# mainboard.net
KiCad netlist of a schematic drawn in EAGLE
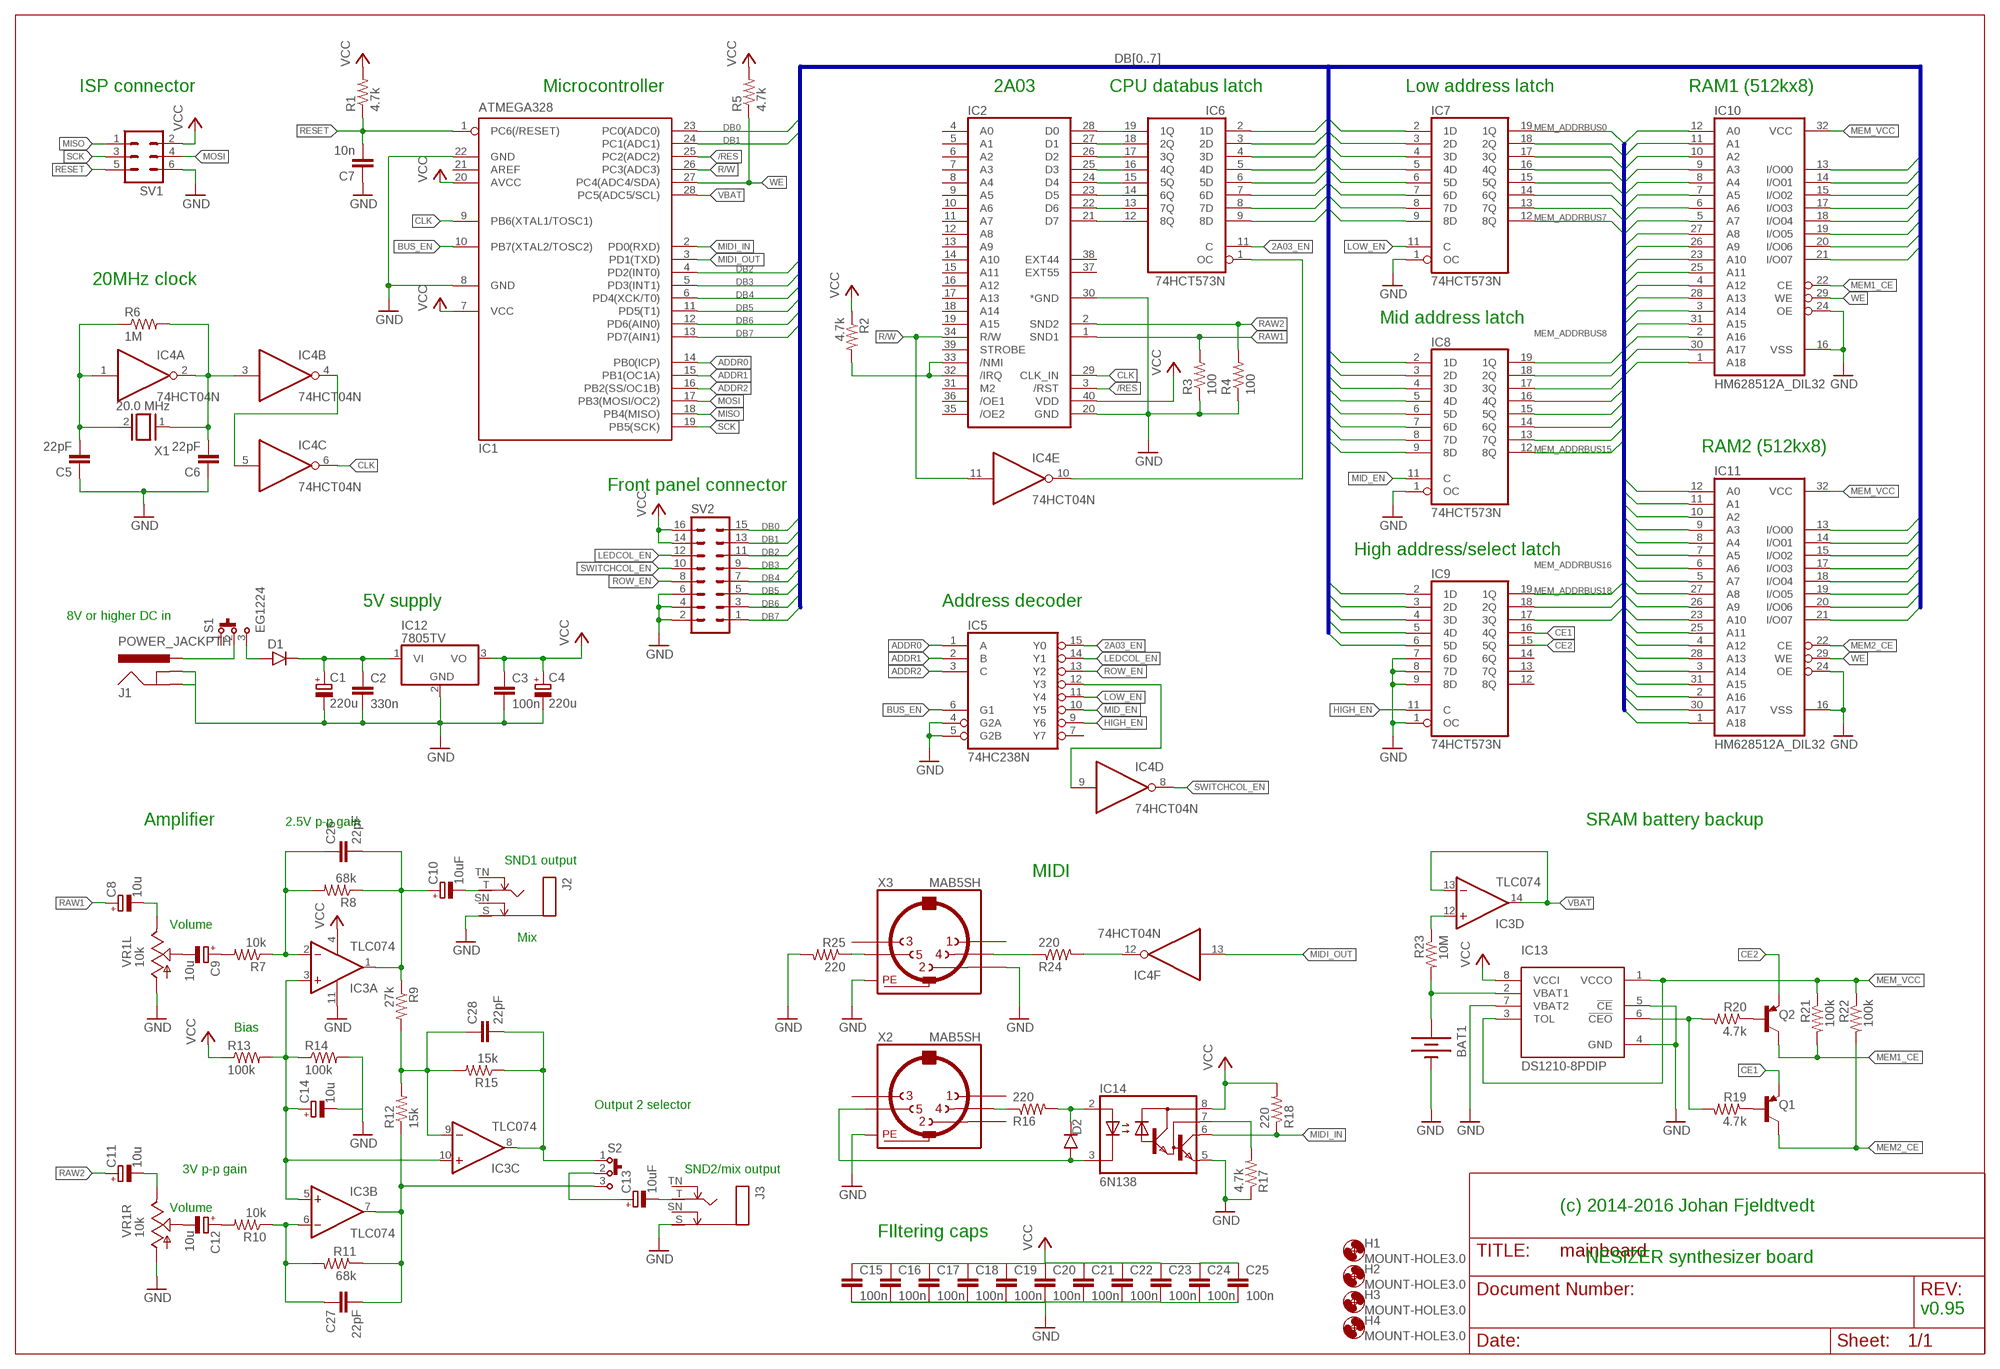
[diagram p0: schematic, sheet 1]

(export (version "E")
  (design (tool "Eeschema 10.0.6"))
  (components
    (comp (ref "BAT1")
      (value "BATTERY20PTH")
      (footprint "eagle-import:BATTCOM_20MM_PTH")
      (libsource (lib "eagle-import") (part "BATTERY20PTH"))
    )
    (comp (ref "C1")
      (value "220u")
      (footprint "eagle-import:E5-10,5")
      (libsource (lib "eagle-import") (part "CPOL-EUE5-10.5"))
    )
    (comp (ref "C2")
      (value "330n")
      (footprint "eagle-import:C025-025X050")
      (libsource (lib "eagle-import") (part "resistor_C-EU025-025X050"))
    )
    (comp (ref "C3")
      (value "100n")
      (footprint "eagle-import:C025-025X050")
      (libsource (lib "eagle-import") (part "C-EU025-025X050"))
    )
    (comp (ref "C4")
      (value "220u")
      (footprint "eagle-import:E5-10,5")
      (libsource (lib "eagle-import") (part "CPOL-EUE5-10.5"))
    )
    (comp (ref "C5")
      (value "22pF")
      (footprint "eagle-import:C2.5-2")
      (libsource (lib "eagle-import") (part "C2.5/2"))
    )
    (comp (ref "C6")
      (value "22pF")
      (footprint "eagle-import:C2.5-2")
      (libsource (lib "eagle-import") (part "C2.5/2"))
    )
    (comp (ref "C7")
      (value "10n")
      (footprint "eagle-import:C2.5-2")
      (libsource (lib "eagle-import") (part "C2.5/2"))
    )
    (comp (ref "C8")
      (value "10u")
      (footprint "eagle-import:E2-5")
      (libsource (lib "eagle-import") (part "CPOL-EUE2-5"))
    )
    (comp (ref "C9")
      (value "10u")
      (footprint "eagle-import:E2-5")
      (libsource (lib "eagle-import") (part "CPOL-EUE2-5"))
    )
    (comp (ref "C10")
      (value "10uF")
      (footprint "eagle-import:E2-5")
      (libsource (lib "eagle-import") (part "CPOL-EUE2-5"))
    )
    (comp (ref "C11")
      (value "10u")
      (footprint "eagle-import:E2-5")
      (libsource (lib "eagle-import") (part "CPOL-EUE2-5"))
    )
    (comp (ref "C12")
      (value "10u")
      (footprint "eagle-import:E2-5")
      (libsource (lib "eagle-import") (part "CPOL-EUE2-5"))
    )
    (comp (ref "C13")
      (value "10uF")
      (footprint "eagle-import:E2-5")
      (libsource (lib "eagle-import") (part "CPOL-EUE2-5"))
    )
    (comp (ref "C14")
      (value "10u")
      (footprint "eagle-import:E2-5")
      (libsource (lib "eagle-import") (part "CPOL-EUE2-5"))
    )
    (comp (ref "C15")
      (value "100n")
      (footprint "eagle-import:C025-025X050")
      (libsource (lib "eagle-import") (part "C-EU025-025X050"))
    )
    (comp (ref "C16")
      (value "100n")
      (footprint "eagle-import:C025-025X050")
      (libsource (lib "eagle-import") (part "C-EU025-025X050"))
    )
    (comp (ref "C17")
      (value "100n")
      (footprint "eagle-import:C025-025X050")
      (libsource (lib "eagle-import") (part "C-EU025-025X050"))
    )
    (comp (ref "C18")
      (value "100n")
      (footprint "eagle-import:C025-025X050")
      (libsource (lib "eagle-import") (part "C-EU025-025X050"))
    )
    (comp (ref "C19")
      (value "100n")
      (footprint "eagle-import:C025-025X050")
      (libsource (lib "eagle-import") (part "C-EU025-025X050"))
    )
    (comp (ref "C20")
      (value "100n")
      (footprint "eagle-import:C025-025X050")
      (libsource (lib "eagle-import") (part "C-EU025-025X050"))
    )
    (comp (ref "C21")
      (value "100n")
      (footprint "eagle-import:C025-025X050")
      (libsource (lib "eagle-import") (part "C-EU025-025X050"))
    )
    (comp (ref "C22")
      (value "100n")
      (footprint "eagle-import:C025-025X050")
      (libsource (lib "eagle-import") (part "C-EU025-025X050"))
    )
    (comp (ref "C23")
      (value "100n")
      (footprint "eagle-import:C025-025X050")
      (libsource (lib "eagle-import") (part "C-EU025-025X050"))
    )
    (comp (ref "C24")
      (value "100n")
      (footprint "eagle-import:C025-025X050")
      (libsource (lib "eagle-import") (part "C-EU025-025X050"))
    )
    (comp (ref "C25")
      (value "100n")
      (footprint "eagle-import:C025-025X050")
      (libsource (lib "eagle-import") (part "C-EU025-025X050"))
    )
    (comp (ref "C26")
      (value "22pF")
      (footprint "eagle-import:C2.5-2")
      (libsource (lib "eagle-import") (part "C2.5/2"))
    )
    (comp (ref "C27")
      (value "22pF")
      (footprint "eagle-import:C2.5-2")
      (libsource (lib "eagle-import") (part "C2.5/2"))
    )
    (comp (ref "C28")
      (value "22pF")
      (footprint "eagle-import:C2.5-2")
      (libsource (lib "eagle-import") (part "C2.5/2"))
    )
    (comp (ref "D1")
      (value "1N400X.3")
      (footprint "eagle-import:DO41-3")
      (libsource (lib "eagle-import") (part "1N400X.3"))
    )
    (comp (ref "D2")
      (value "1N914.3")
      (footprint "eagle-import:DO35-3")
      (libsource (lib "eagle-import") (part "1N914.3"))
    )
    (comp (ref "H1")
      (value "MOUNT-HOLE3.0")
      (footprint "eagle-import:3,0")
      (libsource (lib "eagle-import") (part "MOUNT-HOLE3.0"))
    )
    (comp (ref "H2")
      (value "MOUNT-HOLE3.0")
      (footprint "eagle-import:3,0")
      (libsource (lib "eagle-import") (part "MOUNT-HOLE3.0"))
    )
    (comp (ref "H3")
      (value "MOUNT-HOLE3.0")
      (footprint "eagle-import:3,0")
      (libsource (lib "eagle-import") (part "MOUNT-HOLE3.0"))
    )
    (comp (ref "H4")
      (value "MOUNT-HOLE3.0")
      (footprint "eagle-import:3,0")
      (libsource (lib "eagle-import") (part "MOUNT-HOLE3.0"))
    )
    (comp (ref "IC1")
      (value "ATMEGA328")
      (footprint "eagle-import:DIL28-3")
      (libsource (lib "eagle-import") (part "MEGA8-P"))
    )
    (comp (ref "IC2")
      (value "2A03")
      (footprint "eagle-import:DIL40")
      (libsource (lib "eagle-import") (part "2A03"))
    )
    (comp (ref "IC3")
      (value "TLC074")
      (footprint "eagle-import:DIL14")
      (libsource (lib "eagle-import") (part "TL074P"))
    )
    (comp (ref "IC4")
      (value "74HCT04N")
      (footprint "eagle-import:DIL14")
      (libsource (lib "eagle-import") (part "7404NHCT"))
    )
    (comp (ref "IC5")
      (value "74HC238N")
      (footprint "eagle-import:DIL16")
      (libsource (lib "eagle-import") (part "74138NHC"))
    )
    (comp (ref "IC6")
      (value "74HCT573N")
      (footprint "eagle-import:DIL20")
      (libsource (lib "eagle-import") (part "74573NHCT"))
    )
    (comp (ref "IC7")
      (value "74HCT573N")
      (footprint "eagle-import:DIL20")
      (libsource (lib "eagle-import") (part "74573NHCT"))
    )
    (comp (ref "IC8")
      (value "74HCT573N")
      (footprint "eagle-import:DIL20")
      (libsource (lib "eagle-import") (part "74573NHCT"))
    )
    (comp (ref "IC9")
      (value "74HCT573N")
      (footprint "eagle-import:DIL20")
      (libsource (lib "eagle-import") (part "74573NHCT"))
    )
    (comp (ref "IC10")
      (value "HM628512A_DIL32")
      (footprint "eagle-import:DIL32")
      (libsource (lib "eagle-import") (part "HM628512A_DIL32"))
    )
    (comp (ref "IC11")
      (value "HM628512A_DIL32")
      (footprint "eagle-import:DIL32")
      (libsource (lib "eagle-import") (part "HM628512A_DIL32"))
    )
    (comp (ref "IC12")
      (value "7805TV")
      (footprint "eagle-import:TO220V")
      (libsource (lib "eagle-import") (part "78TV05"))
    )
    (comp (ref "IC13")
      (value "DS1210-8PDIP")
      (footprint "eagle-import:DIL08")
      (libsource (lib "eagle-import") (part "DS1210-8PDIP"))
    )
    (comp (ref "IC14")
      (value "6N138")
      (footprint "eagle-import:DIL08")
      (fields (field (name "MF") "VISHAY/TELEFUNKEN"))
      (libsource (lib "eagle-import") (part "6N138"))
    )
    (comp (ref "J1")
      (value "POWER_JACKPTH")
      (footprint "eagle-import:POWER_JACK_PTH")
      (libsource (lib "eagle-import") (part "POWER_JACKPTH"))
    )
    (comp (ref "J2")
      (value "MONOSW")
      (footprint "eagle-import:NMJ4HCD2")
      (libsource (lib "eagle-import") (part "MONOSW"))
    )
    (comp (ref "J3")
      (value "MONOSW")
      (footprint "eagle-import:NMJ4HCD2")
      (libsource (lib "eagle-import") (part "MONOSW"))
    )
    (comp (ref "Q1")
      (value "BC557")
      (footprint "eagle-import:TO92")
      (libsource (lib "eagle-import") (part "BC557"))
    )
    (comp (ref "Q2")
      (value "BC557")
      (footprint "eagle-import:TO92")
      (libsource (lib "eagle-import") (part "BC557"))
    )
    (comp (ref "R1")
      (value "4.7k")
      (footprint "eagle-import:0207_7")
      (libsource (lib "eagle-import") (part "R-US_0207/7"))
    )
    (comp (ref "R2")
      (value "4.7k")
      (footprint "eagle-import:0207_7")
      (libsource (lib "eagle-import") (part "R-US_0207/7"))
    )
    (comp (ref "R3")
      (value "100")
      (footprint "eagle-import:0207_7")
      (libsource (lib "eagle-import") (part "R-US_0207/7"))
    )
    (comp (ref "R4")
      (value "100")
      (footprint "eagle-import:0207_7")
      (libsource (lib "eagle-import") (part "R-US_0207/7"))
    )
    (comp (ref "R5")
      (value "4.7k")
      (footprint "eagle-import:0207_7")
      (libsource (lib "eagle-import") (part "R-US_0207/7"))
    )
    (comp (ref "R6")
      (value "1M")
      (footprint "eagle-import:0207_7")
      (libsource (lib "eagle-import") (part "R-US_0207/7"))
    )
    (comp (ref "R7")
      (value "10k")
      (footprint "eagle-import:0207_7")
      (libsource (lib "eagle-import") (part "R-US_0207/7"))
    )
    (comp (ref "R8")
      (value "68k")
      (footprint "eagle-import:0207_7")
      (libsource (lib "eagle-import") (part "R-US_0207/7"))
    )
    (comp (ref "R9")
      (value "27k")
      (footprint "eagle-import:0207_7")
      (libsource (lib "eagle-import") (part "R-US_0207/7"))
    )
    (comp (ref "R10")
      (value "10k")
      (footprint "eagle-import:0207_7")
      (libsource (lib "eagle-import") (part "R-US_0207/7"))
    )
    (comp (ref "R11")
      (value "68k")
      (footprint "eagle-import:0207_7")
      (libsource (lib "eagle-import") (part "R-US_0207/7"))
    )
    (comp (ref "R12")
      (value "15k")
      (footprint "eagle-import:0207_7")
      (libsource (lib "eagle-import") (part "R-US_0207/7"))
    )
    (comp (ref "R13")
      (value "100k")
      (footprint "eagle-import:0207_7")
      (libsource (lib "eagle-import") (part "R-US_0207/7"))
    )
    (comp (ref "R14")
      (value "100k")
      (footprint "eagle-import:0207_7")
      (libsource (lib "eagle-import") (part "R-US_0207/7"))
    )
    (comp (ref "R15")
      (value "15k")
      (footprint "eagle-import:0207_7")
      (libsource (lib "eagle-import") (part "R-US_0207/7"))
    )
    (comp (ref "R16")
      (value "220")
      (footprint "eagle-import:0207_7")
      (libsource (lib "eagle-import") (part "R-US_0207/7"))
    )
    (comp (ref "R17")
      (value "4.7k")
      (footprint "eagle-import:0207_7")
      (libsource (lib "eagle-import") (part "R-US_0207/7"))
    )
    (comp (ref "R18")
      (value "220")
      (footprint "eagle-import:0207_7")
      (libsource (lib "eagle-import") (part "R-US_0207/7"))
    )
    (comp (ref "R19")
      (value "4.7k")
      (footprint "eagle-import:0207_7")
      (libsource (lib "eagle-import") (part "R-US_0207/7"))
    )
    (comp (ref "R20")
      (value "4.7k")
      (footprint "eagle-import:0207_7")
      (libsource (lib "eagle-import") (part "R-US_0207/7"))
    )
    (comp (ref "R21")
      (value "100k")
      (footprint "eagle-import:0207_7")
      (libsource (lib "eagle-import") (part "R-US_0207/7"))
    )
    (comp (ref "R22")
      (value "100k")
      (footprint "eagle-import:0207_7")
      (libsource (lib "eagle-import") (part "R-US_0207/7"))
    )
    (comp (ref "R23")
      (value "10M")
      (footprint "eagle-import:0207_7")
      (libsource (lib "eagle-import") (part "R-US_0207/7"))
    )
    (comp (ref "R24")
      (value "220")
      (footprint "eagle-import:0207_7")
      (libsource (lib "eagle-import") (part "R-US_0207/7"))
    )
    (comp (ref "R25")
      (value "220")
      (footprint "eagle-import:0207_7")
      (libsource (lib "eagle-import") (part "R-US_0207/7"))
    )
    (comp (ref "S1")
      (value "EG1224")
      (footprint "eagle-import:EG1224")
      (libsource (lib "eagle-import") (part "EG1224"))
    )
    (comp (ref "S2")
      (value "EG1224")
      (footprint "eagle-import:EG1224")
      (libsource (lib "eagle-import") (part "EG1224"))
    )
    (comp (ref "SV1")
      (value "MA03-2")
      (footprint "eagle-import:MA03-2")
      (libsource (lib "eagle-import") (part "MA03-2"))
    )
    (comp (ref "SV2")
      (value "MA08-2")
      (footprint "eagle-import:MA08-2")
      (libsource (lib "eagle-import") (part "MA08-2"))
    )
    (comp (ref "VR1")
      (value "10k")
      (footprint "eagle-import:ALPS_RK0971221Z0X")
      (libsource (lib "eagle-import") (part "ALPS_RK0971221Z0N"))
    )
    (comp (ref "X1")
      (value "20.0 MHz")
      (footprint "eagle-import:QS")
      (libsource (lib "eagle-import") (part "XTAL/S"))
    )
    (comp (ref "X2")
      (value "MAB5SH")
      (footprint "eagle-import:MAB5SH")
      (libsource (lib "eagle-import") (part "MAB5SH"))
    )
    (comp (ref "X3")
      (value "MAB5SH")
      (footprint "eagle-import:MAB5SH")
      (libsource (lib "eagle-import") (part "MAB5SH"))
    )
  )
  (nets
    (net (code "1") (name "/DB0") (class "Default")
      (node (ref "IC1") (pin "23") (pinfunction "PC0(ADC0)_23") (pintype "bidirectional"))
      (node (ref "IC10") (pin "13") (pinfunction "I/O00_13") (pintype "bidirectional"))
      (node (ref "IC11") (pin "13") (pinfunction "I/O00_13") (pintype "bidirectional"))
      (node (ref "IC6") (pin "2") (pinfunction "1D_2") (pintype "input"))
      (node (ref "IC7") (pin "2") (pinfunction "1D_2") (pintype "input"))
      (node (ref "IC8") (pin "2") (pinfunction "1D_2") (pintype "input"))
      (node (ref "IC9") (pin "2") (pinfunction "1D_2") (pintype "input"))
      (node (ref "SV2") (pin "15") (pinfunction "15_15") (pintype "passive"))
    )
    (net (code "2") (name "/DB1") (class "Default")
      (node (ref "IC1") (pin "24") (pinfunction "PC1(ADC1)_24") (pintype "bidirectional"))
      (node (ref "IC10") (pin "14") (pinfunction "I/O01_14") (pintype "bidirectional"))
      (node (ref "IC11") (pin "14") (pinfunction "I/O01_14") (pintype "bidirectional"))
      (node (ref "IC6") (pin "3") (pinfunction "2D_3") (pintype "input"))
      (node (ref "IC7") (pin "3") (pinfunction "2D_3") (pintype "input"))
      (node (ref "IC8") (pin "3") (pinfunction "2D_3") (pintype "input"))
      (node (ref "IC9") (pin "3") (pinfunction "2D_3") (pintype "input"))
      (node (ref "SV2") (pin "13") (pinfunction "13_13") (pintype "passive"))
    )
    (net (code "3") (name "/DB2") (class "Default")
      (node (ref "IC1") (pin "4") (pinfunction "PD2(INT0)_4") (pintype "bidirectional"))
      (node (ref "IC10") (pin "15") (pinfunction "I/O02_15") (pintype "bidirectional"))
      (node (ref "IC11") (pin "15") (pinfunction "I/O02_15") (pintype "bidirectional"))
      (node (ref "IC6") (pin "4") (pinfunction "3D_4") (pintype "input"))
      (node (ref "IC7") (pin "4") (pinfunction "3D_4") (pintype "input"))
      (node (ref "IC8") (pin "4") (pinfunction "3D_4") (pintype "input"))
      (node (ref "IC9") (pin "4") (pinfunction "3D_4") (pintype "input"))
      (node (ref "SV2") (pin "11") (pinfunction "11_11") (pintype "passive"))
    )
    (net (code "4") (name "/DB3") (class "Default")
      (node (ref "IC1") (pin "5") (pinfunction "PD3(INT1)_5") (pintype "bidirectional"))
      (node (ref "IC10") (pin "17") (pinfunction "I/O03_17") (pintype "bidirectional"))
      (node (ref "IC11") (pin "17") (pinfunction "I/O03_17") (pintype "bidirectional"))
      (node (ref "IC6") (pin "5") (pinfunction "4D_5") (pintype "input"))
      (node (ref "IC7") (pin "5") (pinfunction "4D_5") (pintype "input"))
      (node (ref "IC8") (pin "5") (pinfunction "4D_5") (pintype "input"))
      (node (ref "IC9") (pin "5") (pinfunction "4D_5") (pintype "input"))
      (node (ref "SV2") (pin "9") (pinfunction "9_9") (pintype "passive"))
    )
    (net (code "5") (name "/DB4") (class "Default")
      (node (ref "IC1") (pin "6") (pinfunction "PD4(XCK/T0)_6") (pintype "bidirectional"))
      (node (ref "IC10") (pin "18") (pinfunction "I/O04_18") (pintype "bidirectional"))
      (node (ref "IC11") (pin "18") (pinfunction "I/O04_18") (pintype "bidirectional"))
      (node (ref "IC6") (pin "6") (pinfunction "5D_6") (pintype "input"))
      (node (ref "IC7") (pin "6") (pinfunction "5D_6") (pintype "input"))
      (node (ref "IC8") (pin "6") (pinfunction "5D_6") (pintype "input"))
      (node (ref "IC9") (pin "6") (pinfunction "5D_6") (pintype "input"))
      (node (ref "SV2") (pin "7") (pinfunction "7_7") (pintype "passive"))
    )
    (net (code "6") (name "/DB5") (class "Default")
      (node (ref "IC1") (pin "11") (pinfunction "PD5(T1)_11") (pintype "bidirectional"))
      (node (ref "IC10") (pin "19") (pinfunction "I/O05_19") (pintype "bidirectional"))
      (node (ref "IC11") (pin "19") (pinfunction "I/O05_19") (pintype "bidirectional"))
      (node (ref "IC6") (pin "7") (pinfunction "6D_7") (pintype "input"))
      (node (ref "IC7") (pin "7") (pinfunction "6D_7") (pintype "input"))
      (node (ref "IC8") (pin "7") (pinfunction "6D_7") (pintype "input"))
      (node (ref "SV2") (pin "5") (pinfunction "5_5") (pintype "passive"))
    )
    (net (code "7") (name "/DB6") (class "Default")
      (node (ref "IC1") (pin "12") (pinfunction "PD6(AIN0)_12") (pintype "bidirectional"))
      (node (ref "IC10") (pin "20") (pinfunction "I/O06_20") (pintype "bidirectional"))
      (node (ref "IC11") (pin "20") (pinfunction "I/O06_20") (pintype "bidirectional"))
      (node (ref "IC6") (pin "8") (pinfunction "7D_8") (pintype "input"))
      (node (ref "IC7") (pin "8") (pinfunction "7D_8") (pintype "input"))
      (node (ref "IC8") (pin "8") (pinfunction "7D_8") (pintype "input"))
      (node (ref "SV2") (pin "3") (pinfunction "3_3") (pintype "passive"))
    )
    (net (code "8") (name "/DB7") (class "Default")
      (node (ref "IC1") (pin "13") (pinfunction "PD7(AIN1)_13") (pintype "bidirectional"))
      (node (ref "IC10") (pin "21") (pinfunction "I/O07_21") (pintype "bidirectional"))
      (node (ref "IC11") (pin "21") (pinfunction "I/O07_21") (pintype "bidirectional"))
      (node (ref "IC6") (pin "9") (pinfunction "8D_9") (pintype "input"))
      (node (ref "IC7") (pin "9") (pinfunction "8D_9") (pintype "input"))
      (node (ref "IC8") (pin "9") (pinfunction "8D_9") (pintype "input"))
      (node (ref "SV2") (pin "1") (pinfunction "1_1") (pintype "passive"))
    )
    (net (code "10") (name "/MEM_ADDRBUS0") (class "Default")
      (node (ref "IC10") (pin "12") (pinfunction "A0_12") (pintype "input"))
      (node (ref "IC11") (pin "12") (pinfunction "A0_12") (pintype "input"))
      (node (ref "IC7") (pin "19") (pinfunction "1Q_19") (pintype "tri_state"))
    )
    (net (code "11") (name "/MEM_ADDRBUS1") (class "Default")
      (node (ref "IC10") (pin "11") (pinfunction "A1_11") (pintype "input"))
      (node (ref "IC11") (pin "11") (pinfunction "A1_11") (pintype "input"))
      (node (ref "IC7") (pin "18") (pinfunction "2Q_18") (pintype "tri_state"))
    )
    (net (code "12") (name "/MEM_ADDRBUS2") (class "Default")
      (node (ref "IC10") (pin "10") (pinfunction "A2_10") (pintype "input"))
      (node (ref "IC11") (pin "10") (pinfunction "A2_10") (pintype "input"))
      (node (ref "IC7") (pin "17") (pinfunction "3Q_17") (pintype "tri_state"))
    )
    (net (code "13") (name "/MEM_ADDRBUS3") (class "Default")
      (node (ref "IC10") (pin "9") (pinfunction "A3_9") (pintype "input"))
      (node (ref "IC11") (pin "9") (pinfunction "A3_9") (pintype "input"))
      (node (ref "IC7") (pin "16") (pinfunction "4Q_16") (pintype "tri_state"))
    )
    (net (code "14") (name "/MEM_ADDRBUS4") (class "Default")
      (node (ref "IC10") (pin "8") (pinfunction "A4_8") (pintype "input"))
      (node (ref "IC11") (pin "8") (pinfunction "A4_8") (pintype "input"))
      (node (ref "IC7") (pin "15") (pinfunction "5Q_15") (pintype "tri_state"))
    )
    (net (code "15") (name "/MEM_ADDRBUS5") (class "Default")
      (node (ref "IC10") (pin "7") (pinfunction "A5_7") (pintype "input"))
      (node (ref "IC11") (pin "7") (pinfunction "A5_7") (pintype "input"))
      (node (ref "IC7") (pin "14") (pinfunction "6Q_14") (pintype "tri_state"))
    )
    (net (code "16") (name "/MEM_ADDRBUS6") (class "Default")
      (node (ref "IC10") (pin "6") (pinfunction "A6_6") (pintype "input"))
      (node (ref "IC11") (pin "6") (pinfunction "A6_6") (pintype "input"))
      (node (ref "IC7") (pin "13") (pinfunction "7Q_13") (pintype "tri_state"))
    )
    (net (code "17") (name "/MEM_ADDRBUS7") (class "Default")
      (node (ref "IC10") (pin "5") (pinfunction "A7_5") (pintype "input"))
      (node (ref "IC11") (pin "5") (pinfunction "A7_5") (pintype "input"))
      (node (ref "IC7") (pin "12") (pinfunction "8Q_12") (pintype "tri_state"))
    )
    (net (code "18") (name "/MEM_ADDRBUS8") (class "Default")
      (node (ref "IC10") (pin "27") (pinfunction "A8_27") (pintype "input"))
      (node (ref "IC11") (pin "27") (pinfunction "A8_27") (pintype "input"))
      (node (ref "IC8") (pin "19") (pinfunction "1Q_19") (pintype "tri_state"))
    )
    (net (code "19") (name "/MEM_ADDRBUS9") (class "Default")
      (node (ref "IC10") (pin "26") (pinfunction "A9_26") (pintype "input"))
      (node (ref "IC11") (pin "26") (pinfunction "A9_26") (pintype "input"))
      (node (ref "IC8") (pin "18") (pinfunction "2Q_18") (pintype "tri_state"))
    )
    (net (code "20") (name "/MEM_ADDRBUS10") (class "Default")
      (node (ref "IC10") (pin "23") (pinfunction "A10_23") (pintype "input"))
      (node (ref "IC11") (pin "23") (pinfunction "A10_23") (pintype "input"))
      (node (ref "IC8") (pin "17") (pinfunction "3Q_17") (pintype "tri_state"))
    )
    (net (code "21") (name "/MEM_ADDRBUS11") (class "Default")
      (node (ref "IC10") (pin "25") (pinfunction "A11_25") (pintype "input"))
      (node (ref "IC11") (pin "25") (pinfunction "A11_25") (pintype "input"))
      (node (ref "IC8") (pin "16") (pinfunction "4Q_16") (pintype "tri_state"))
    )
    (net (code "22") (name "/MEM_ADDRBUS12") (class "Default")
      (node (ref "IC10") (pin "4") (pinfunction "A12_4") (pintype "input"))
      (node (ref "IC11") (pin "4") (pinfunction "A12_4") (pintype "input"))
      (node (ref "IC8") (pin "15") (pinfunction "5Q_15") (pintype "tri_state"))
    )
    (net (code "23") (name "/MEM_ADDRBUS13") (class "Default")
      (node (ref "IC10") (pin "28") (pinfunction "A13_28") (pintype "input"))
      (node (ref "IC11") (pin "28") (pinfunction "A13_28") (pintype "input"))
      (node (ref "IC8") (pin "14") (pinfunction "6Q_14") (pintype "tri_state"))
    )
    (net (code "24") (name "/MEM_ADDRBUS14") (class "Default")
      (node (ref "IC10") (pin "3") (pinfunction "A14_3") (pintype "input"))
      (node (ref "IC11") (pin "3") (pinfunction "A14_3") (pintype "input"))
      (node (ref "IC8") (pin "13") (pinfunction "7Q_13") (pintype "tri_state"))
    )
    (net (code "25") (name "/MEM_ADDRBUS15") (class "Default")
      (node (ref "IC10") (pin "31") (pinfunction "A15_31") (pintype "input"))
      (node (ref "IC11") (pin "31") (pinfunction "A15_31") (pintype "input"))
      (node (ref "IC8") (pin "12") (pinfunction "8Q_12") (pintype "tri_state"))
    )
    (net (code "26") (name "/MEM_ADDRBUS16") (class "Default")
      (node (ref "IC10") (pin "2") (pinfunction "A16_2") (pintype "input"))
      (node (ref "IC11") (pin "2") (pinfunction "A16_2") (pintype "input"))
      (node (ref "IC9") (pin "19") (pinfunction "1Q_19") (pintype "tri_state"))
    )
    (net (code "27") (name "/MEM_ADDRBUS17") (class "Default")
      (node (ref "IC10") (pin "30") (pinfunction "A17_30") (pintype "input"))
      (node (ref "IC11") (pin "30") (pinfunction "A17_30") (pintype "input"))
      (node (ref "IC9") (pin "18") (pinfunction "2Q_18") (pintype "tri_state"))
    )
    (net (code "28") (name "/MEM_ADDRBUS18") (class "Default")
      (node (ref "IC10") (pin "1") (pinfunction "A18_1") (pintype "input"))
      (node (ref "IC11") (pin "1") (pinfunction "A18_1") (pintype "input"))
      (node (ref "IC9") (pin "17") (pinfunction "3Q_17") (pintype "tri_state"))
    )
    (net (code "29") (name "2A03_EN") (class "Default")
      (node (ref "IC5") (pin "15") (pinfunction "Y0_15") (pintype "output"))
      (node (ref "IC6") (pin "11") (pinfunction "C_11") (pintype "input"))
    )
    (net (code "30") (name "ADDR0") (class "Default")
      (node (ref "IC1") (pin "14") (pinfunction "PB0(ICP)_14") (pintype "bidirectional"))
      (node (ref "IC5") (pin "1") (pinfunction "A_1") (pintype "input"))
    )
    (net (code "31") (name "ADDR1") (class "Default")
      (node (ref "IC1") (pin "15") (pinfunction "PB1(OC1A)_15") (pintype "bidirectional"))
      (node (ref "IC5") (pin "2") (pinfunction "B_2") (pintype "input"))
    )
    (net (code "32") (name "ADDR2") (class "Default")
      (node (ref "IC1") (pin "16") (pinfunction "PB2(SS/OC1B)_16") (pintype "bidirectional"))
      (node (ref "IC5") (pin "3") (pinfunction "C_3") (pintype "input"))
    )
    (net (code "33") (name "BUS_EN") (class "Default")
      (node (ref "IC1") (pin "10") (pinfunction "PB7(XTAL2/TOSC2)_10") (pintype "bidirectional"))
      (node (ref "IC5") (pin "6") (pinfunction "G1_6") (pintype "input"))
    )
    (net (code "34") (name "CE1") (class "Default")
      (node (ref "IC9") (pin "16") (pinfunction "4Q_16") (pintype "tri_state"))
      (node (ref "Q1") (pin "1") (pinfunction "E_1") (pintype "passive"))
    )
    (net (code "35") (name "CE2") (class "Default")
      (node (ref "IC9") (pin "15") (pinfunction "5Q_15") (pintype "tri_state"))
      (node (ref "Q2") (pin "1") (pinfunction "E_1") (pintype "passive"))
    )
    (net (code "36") (name "CLK") (class "Default")
      (node (ref "IC1") (pin "9") (pinfunction "PB6(XTAL1/TOSC1)_9") (pintype "bidirectional"))
      (node (ref "IC2") (pin "29") (pinfunction "CLK_IN_29") (pintype "input"))
      (node (ref "IC4") (pin "6") (pinfunction "O_6") (pintype "output"))
    )
    (net (code "37") (name "GND") (class "Default")
      (node (ref "BAT1") (pin "2") (pinfunction "-_2") (pintype "power_in"))
      (node (ref "C1") (pin "-") (pinfunction "-_-") (pintype "passive"))
      (node (ref "C14") (pin "-") (pinfunction "-_-") (pintype "passive"))
      (node (ref "C15") (pin "2") (pinfunction "2_2") (pintype "passive"))
      (node (ref "C16") (pin "2") (pinfunction "2_2") (pintype "passive"))
      (node (ref "C17") (pin "2") (pinfunction "2_2") (pintype "passive"))
      (node (ref "C18") (pin "2") (pinfunction "2_2") (pintype "passive"))
      (node (ref "C19") (pin "2") (pinfunction "2_2") (pintype "passive"))
      (node (ref "C2") (pin "2") (pinfunction "2_2") (pintype "passive"))
      (node (ref "C20") (pin "2") (pinfunction "2_2") (pintype "passive"))
      (node (ref "C21") (pin "2") (pinfunction "2_2") (pintype "passive"))
      (node (ref "C22") (pin "2") (pinfunction "2_2") (pintype "passive"))
      (node (ref "C23") (pin "2") (pinfunction "2_2") (pintype "passive"))
      (node (ref "C24") (pin "2") (pinfunction "2_2") (pintype "passive"))
      (node (ref "C25") (pin "2") (pinfunction "2_2") (pintype "passive"))
      (node (ref "C3") (pin "2") (pinfunction "2_2") (pintype "passive"))
      (node (ref "C4") (pin "-") (pinfunction "-_-") (pintype "passive"))
      (node (ref "C5") (pin "1") (pinfunction "1_1") (pintype "passive"))
      (node (ref "C6") (pin "1") (pinfunction "1_1") (pintype "passive"))
      (node (ref "C7") (pin "1") (pinfunction "1_1") (pintype "passive"))
      (node (ref "IC1") (pin "22") (pinfunction "GND_22") (pintype "power_in"))
      (node (ref "IC1") (pin "8") (pinfunction "GND_8") (pintype "power_in"))
      (node (ref "IC10") (pin "16") (pinfunction "VSS_16") (pintype "power_in"))
      (node (ref "IC10") (pin "24") (pinfunction "OE_24") (pintype "input"))
      (node (ref "IC11") (pin "16") (pinfunction "VSS_16") (pintype "power_in"))
      (node (ref "IC11") (pin "24") (pinfunction "OE_24") (pintype "input"))
      (node (ref "IC12") (pin "2") (pinfunction "GND_2") (pintype "passive"))
      (node (ref "IC13") (pin "4") (pinfunction "GND_4") (pintype "bidirectional"))
      (node (ref "IC13") (pin "5") (pinfunction "~{CE}_5") (pintype "bidirectional"))
      (node (ref "IC13") (pin "7") (pinfunction "VBAT2_7") (pintype "bidirectional"))
      (node (ref "IC14") (pin "5") (pinfunction "GND_5") (pintype "passive"))
      (node (ref "IC2") (pin "20") (pinfunction "GND_20") (pintype "power_in"))
      (node (ref "IC2") (pin "30") (pinfunction "*GND_30") (pintype "output"))
      (node (ref "IC3") (pin "11") (pinfunction "V-_11") (pintype "power_in"))
      (node (ref "IC5") (pin "4") (pinfunction "G2A_4") (pintype "input"))
      (node (ref "IC5") (pin "5") (pinfunction "G2B_5") (pintype "input"))
      (node (ref "IC7") (pin "1") (pinfunction "OC_1") (pintype "input"))
      (node (ref "IC8") (pin "1") (pinfunction "OC_1") (pintype "input"))
      (node (ref "IC9") (pin "1") (pinfunction "OC_1") (pintype "input"))
      (node (ref "IC9") (pin "7") (pinfunction "6D_7") (pintype "input"))
      (node (ref "IC9") (pin "8") (pinfunction "7D_8") (pintype "input"))
      (node (ref "IC9") (pin "9") (pinfunction "8D_9") (pintype "input"))
      (node (ref "J1") (pin "GND") (pinfunction "GND_GND") (pintype "bidirectional"))
      (node (ref "J1") (pin "GNDBREAK") (pinfunction "GNDBREAK_GNDBREAK") (pintype "bidirectional"))
      (node (ref "J2") (pin "S") (pinfunction "S_S") (pintype "passive"))
      (node (ref "J3") (pin "S") (pinfunction "S_S") (pintype "passive"))
      (node (ref "R14") (pin "2") (pinfunction "2_2") (pintype "passive"))
      (node (ref "R17") (pin "1") (pinfunction "1_1") (pintype "passive"))
      (node (ref "R25") (pin "2") (pinfunction "2_2") (pintype "passive"))
      (node (ref "R3") (pin "1") (pinfunction "1_1") (pintype "passive"))
      (node (ref "R4") (pin "1") (pinfunction "1_1") (pintype "passive"))
      (node (ref "SV1") (pin "6") (pinfunction "6_6") (pintype "passive"))
      (node (ref "SV2") (pin "2") (pinfunction "2_2") (pintype "passive"))
      (node (ref "SV2") (pin "4") (pinfunction "4_4") (pintype "passive"))
      (node (ref "SV2") (pin "6") (pinfunction "6_6") (pintype "passive"))
      (node (ref "VR1") (pin "G1") (pinfunction "1_G1") (pintype "passive"))
      (node (ref "VR1") (pin "G2") (pinfunction "1_G2") (pintype "passive"))
      (node (ref "X2") (pin "PE") (pinfunction "PE_PE") (pintype "power_in"))
      (node (ref "X2") (pin "PE@") (pinfunction "PE_PE@") (pintype "power_in"))
      (node (ref "X3") (pin "2") (pinfunction "2_2") (pintype "passive"))
      (node (ref "X3") (pin "PE") (pinfunction "PE_PE") (pintype "power_in"))
      (node (ref "X3") (pin "PE@") (pinfunction "PE_PE@") (pintype "power_in"))
    )
    (net (code "38") (name "HIGH_EN") (class "Default")
      (node (ref "IC5") (pin "9") (pinfunction "Y6_9") (pintype "output"))
      (node (ref "IC9") (pin "11") (pinfunction "C_11") (pintype "input"))
    )
    (net (code "39") (name "LEDCOL_EN") (class "Default")
      (node (ref "IC5") (pin "14") (pinfunction "Y1_14") (pintype "output"))
      (node (ref "SV2") (pin "12") (pinfunction "12_12") (pintype "passive"))
    )
    (net (code "40") (name "LOW_EN") (class "Default")
      (node (ref "IC5") (pin "11") (pinfunction "Y4_11") (pintype "output"))
      (node (ref "IC7") (pin "11") (pinfunction "C_11") (pintype "input"))
    )
    (net (code "41") (name "MEM1_CE") (class "Default")
      (node (ref "IC10") (pin "22") (pinfunction "CE_22") (pintype "input"))
      (node (ref "Q2") (pin "3") (pinfunction "C_3") (pintype "passive"))
      (node (ref "R21") (pin "2") (pinfunction "2_2") (pintype "passive"))
    )
    (net (code "42") (name "MEM2_CE") (class "Default")
      (node (ref "IC11") (pin "22") (pinfunction "CE_22") (pintype "input"))
      (node (ref "Q1") (pin "3") (pinfunction "C_3") (pintype "passive"))
      (node (ref "R22") (pin "2") (pinfunction "2_2") (pintype "passive"))
    )
    (net (code "43") (name "MEM_VCC") (class "Default")
      (node (ref "IC10") (pin "32") (pinfunction "VCC_32") (pintype "power_in"))
      (node (ref "IC11") (pin "32") (pinfunction "VCC_32") (pintype "power_in"))
      (node (ref "IC13") (pin "1") (pinfunction "VCCO_1") (pintype "bidirectional"))
      (node (ref "IC13") (pin "3") (pinfunction "TOL_3") (pintype "bidirectional"))
      (node (ref "R21") (pin "1") (pinfunction "1_1") (pintype "passive"))
      (node (ref "R22") (pin "1") (pinfunction "1_1") (pintype "passive"))
    )
    (net (code "44") (name "MIDI_IN") (class "Default")
      (node (ref "IC1") (pin "2") (pinfunction "PD0(RXD)_2") (pintype "bidirectional"))
      (node (ref "IC14") (pin "6") (pinfunction "VO_6") (pintype "passive"))
      (node (ref "R18") (pin "1") (pinfunction "1_1") (pintype "passive"))
    )
    (net (code "45") (name "MIDI_OUT") (class "Default")
      (node (ref "IC1") (pin "3") (pinfunction "PD1(TXD)_3") (pintype "bidirectional"))
      (node (ref "IC4") (pin "13") (pinfunction "I_13") (pintype "input"))
    )
    (net (code "46") (name "MID_EN") (class "Default")
      (node (ref "IC5") (pin "10") (pinfunction "Y5_10") (pintype "output"))
      (node (ref "IC8") (pin "11") (pinfunction "C_11") (pintype "input"))
    )
    (net (code "47") (name "MISO") (class "Default")
      (node (ref "IC1") (pin "18") (pinfunction "PB4(MISO)_18") (pintype "bidirectional"))
      (node (ref "SV1") (pin "1") (pinfunction "1_1") (pintype "passive"))
    )
    (net (code "48") (name "MOSI") (class "Default")
      (node (ref "IC1") (pin "17") (pinfunction "PB3(MOSI/OC2)_17") (pintype "bidirectional"))
      (node (ref "SV1") (pin "4") (pinfunction "4_4") (pintype "passive"))
    )
    (net (code "49") (name "Net-(BAT1-+)") (class "Default")
      (node (ref "BAT1") (pin "1") (pinfunction "+_1") (pintype "power_in"))
      (node (ref "IC13") (pin "2") (pinfunction "VBAT1_2") (pintype "bidirectional"))
      (node (ref "R23") (pin "2") (pinfunction "2_2") (pintype "passive"))
    )
    (net (code "50") (name "Net-(C9-Pad+)") (class "Default")
      (node (ref "C9") (pin "+") (pinfunction "+_+") (pintype "passive"))
      (node (ref "R7") (pin "2") (pinfunction "2_2") (pintype "passive"))
    )
    (net (code "51") (name "Net-(C10-Pad-)") (class "Default")
      (node (ref "C10") (pin "-") (pinfunction "-_-") (pintype "passive"))
      (node (ref "J2") (pin "T") (pinfunction "T_T") (pintype "passive"))
    )
    (net (code "52") (name "Net-(C12-Pad+)") (class "Default")
      (node (ref "C12") (pin "+") (pinfunction "+_+") (pintype "passive"))
      (node (ref "R10") (pin "2") (pinfunction "2_2") (pintype "passive"))
    )
    (net (code "53") (name "Net-(C13-Pad+)") (class "Default")
      (node (ref "C13") (pin "+") (pinfunction "+_+") (pintype "passive"))
      (node (ref "S2") (pin "2") (pinfunction "2_2") (pintype "passive"))
    )
    (net (code "54") (name "Net-(C13-Pad-)") (class "Default")
      (node (ref "C13") (pin "-") (pinfunction "-_-") (pintype "passive"))
      (node (ref "J3") (pin "T") (pinfunction "T_T") (pintype "passive"))
    )
    (net (code "55") (name "Net-(D1-PadA)") (class "Default")
      (node (ref "D1") (pin "A") (pinfunction "A_A") (pintype "passive"))
      (node (ref "S1") (pin "3") (pinfunction "3_3") (pintype "passive"))
    )
    (net (code "56") (name "Net-(IC2-D0)") (class "Default")
      (node (ref "IC2") (pin "28") (pinfunction "D0_28") (pintype "bidirectional"))
      (node (ref "IC6") (pin "19") (pinfunction "1Q_19") (pintype "tri_state"))
    )
    (net (code "57") (name "Net-(IC2-D1)") (class "Default")
      (node (ref "IC2") (pin "27") (pinfunction "D1_27") (pintype "bidirectional"))
      (node (ref "IC6") (pin "18") (pinfunction "2Q_18") (pintype "tri_state"))
    )
    (net (code "58") (name "Net-(IC2-D2)") (class "Default")
      (node (ref "IC2") (pin "26") (pinfunction "D2_26") (pintype "bidirectional"))
      (node (ref "IC6") (pin "17") (pinfunction "3Q_17") (pintype "tri_state"))
    )
    (net (code "59") (name "Net-(IC2-D3)") (class "Default")
      (node (ref "IC2") (pin "25") (pinfunction "D3_25") (pintype "bidirectional"))
      (node (ref "IC6") (pin "16") (pinfunction "4Q_16") (pintype "tri_state"))
    )
    (net (code "60") (name "Net-(IC2-D4)") (class "Default")
      (node (ref "IC2") (pin "24") (pinfunction "D4_24") (pintype "bidirectional"))
      (node (ref "IC6") (pin "15") (pinfunction "5Q_15") (pintype "tri_state"))
    )
    (net (code "61") (name "Net-(IC2-D5)") (class "Default")
      (node (ref "IC2") (pin "23") (pinfunction "D5_23") (pintype "bidirectional"))
      (node (ref "IC6") (pin "14") (pinfunction "6Q_14") (pintype "tri_state"))
    )
    (net (code "62") (name "Net-(IC2-D6)") (class "Default")
      (node (ref "IC2") (pin "22") (pinfunction "D6_22") (pintype "bidirectional"))
      (node (ref "IC6") (pin "13") (pinfunction "7Q_13") (pintype "tri_state"))
    )
    (net (code "63") (name "Net-(IC2-D7)") (class "Default")
      (node (ref "IC2") (pin "21") (pinfunction "D7_21") (pintype "bidirectional"))
      (node (ref "IC6") (pin "12") (pinfunction "8Q_12") (pintype "tri_state"))
    )
    (net (code "64") (name "Net-(IC2-{slash}IRQ)") (class "Default")
      (node (ref "IC2") (pin "32") (pinfunction "/IRQ_32") (pintype "input"))
      (node (ref "IC2") (pin "33") (pinfunction "/NMI_33") (pintype "input"))
      (node (ref "R2") (pin "2") (pinfunction "2_2") (pintype "passive"))
    )
    (net (code "65") (name "Net-(IC3A-+IN)") (class "Default")
      (node (ref "C14") (pin "+") (pinfunction "+_+") (pintype "passive"))
      (node (ref "IC3") (pin "10") (pinfunction "+IN_10") (pintype "input"))
      (node (ref "IC3") (pin "3") (pinfunction "+IN_3") (pintype "input"))
      (node (ref "IC3") (pin "5") (pinfunction "+IN_5") (pintype "input"))
      (node (ref "R13") (pin "2") (pinfunction "2_2") (pintype "passive"))
      (node (ref "R14") (pin "1") (pinfunction "1_1") (pintype "passive"))
    )
    (net (code "66") (name "Net-(IC3A--IN)") (class "Default")
      (node (ref "C26") (pin "1") (pinfunction "1_1") (pintype "passive"))
      (node (ref "IC3") (pin "2") (pinfunction "-IN_2") (pintype "input"))
      (node (ref "R7") (pin "1") (pinfunction "1_1") (pintype "passive"))
      (node (ref "R8") (pin "2") (pinfunction "2_2") (pintype "passive"))
    )
    (net (code "67") (name "Net-(IC3A-OUT)") (class "Default")
      (node (ref "C10") (pin "+") (pinfunction "+_+") (pintype "passive"))
      (node (ref "C26") (pin "2") (pinfunction "2_2") (pintype "passive"))
      (node (ref "IC3") (pin "1") (pinfunction "OUT_1") (pintype "output"))
      (node (ref "R8") (pin "1") (pinfunction "1_1") (pintype "passive"))
      (node (ref "R9") (pin "1") (pinfunction "1_1") (pintype "passive"))
    )
    (net (code "68") (name "Net-(IC3B--IN)") (class "Default")
      (node (ref "C27") (pin "1") (pinfunction "1_1") (pintype "passive"))
      (node (ref "IC3") (pin "6") (pinfunction "-IN_6") (pintype "input"))
      (node (ref "R10") (pin "1") (pinfunction "1_1") (pintype "passive"))
      (node (ref "R11") (pin "2") (pinfunction "2_2") (pintype "passive"))
    )
    (net (code "69") (name "Net-(IC3B-OUT)") (class "Default")
      (node (ref "C27") (pin "2") (pinfunction "2_2") (pintype "passive"))
      (node (ref "IC3") (pin "7") (pinfunction "OUT_7") (pintype "output"))
      (node (ref "R11") (pin "1") (pinfunction "1_1") (pintype "passive"))
      (node (ref "R12") (pin "1") (pinfunction "1_1") (pintype "passive"))
      (node (ref "S2") (pin "3") (pinfunction "3_3") (pintype "passive"))
    )
    (net (code "70") (name "Net-(IC3C--IN)") (class "Default")
      (node (ref "C28") (pin "1") (pinfunction "1_1") (pintype "passive"))
      (node (ref "IC3") (pin "9") (pinfunction "-IN_9") (pintype "input"))
      (node (ref "R12") (pin "2") (pinfunction "2_2") (pintype "passive"))
      (node (ref "R15") (pin "2") (pinfunction "2_2") (pintype "passive"))
      (node (ref "R9") (pin "2") (pinfunction "2_2") (pintype "passive"))
    )
    (net (code "71") (name "Net-(IC3C-OUT)") (class "Default")
      (node (ref "C28") (pin "2") (pinfunction "2_2") (pintype "passive"))
      (node (ref "IC3") (pin "8") (pinfunction "OUT_8") (pintype "output"))
      (node (ref "R15") (pin "1") (pinfunction "1_1") (pintype "passive"))
      (node (ref "S2") (pin "1") (pinfunction "1_1") (pintype "passive"))
    )
    (net (code "72") (name "Net-(IC3D-+IN)") (class "Default")
      (node (ref "IC3") (pin "12") (pinfunction "+IN_12") (pintype "input"))
      (node (ref "R23") (pin "1") (pinfunction "1_1") (pintype "passive"))
    )
    (net (code "73") (name "Net-(IC4A-I)") (class "Default")
      (node (ref "C5") (pin "2") (pinfunction "2_2") (pintype "passive"))
      (node (ref "IC4") (pin "1") (pinfunction "I_1") (pintype "input"))
      (node (ref "R6") (pin "1") (pinfunction "1_1") (pintype "passive"))
      (node (ref "X1") (pin "2") (pinfunction "2_2") (pintype "passive"))
    )
    (net (code "74") (name "Net-(IC4A-O)") (class "Default")
      (node (ref "C6") (pin "2") (pinfunction "2_2") (pintype "passive"))
      (node (ref "IC4") (pin "2") (pinfunction "O_2") (pintype "output"))
      (node (ref "IC4") (pin "3") (pinfunction "I_3") (pintype "input"))
      (node (ref "R6") (pin "2") (pinfunction "2_2") (pintype "passive"))
      (node (ref "X1") (pin "1") (pinfunction "1_1") (pintype "passive"))
    )
    (net (code "75") (name "Net-(IC4B-O)") (class "Default")
      (node (ref "IC4") (pin "4") (pinfunction "O_4") (pintype "output"))
      (node (ref "IC4") (pin "5") (pinfunction "I_5") (pintype "input"))
    )
    (net (code "76") (name "Net-(IC4D-I)") (class "Default")
      (node (ref "IC4") (pin "9") (pinfunction "I_9") (pintype "input"))
      (node (ref "IC5") (pin "12") (pinfunction "Y3_12") (pintype "output"))
    )
    (net (code "77") (name "Net-(IC4E-O)") (class "Default")
      (node (ref "IC4") (pin "10") (pinfunction "O_10") (pintype "output"))
      (node (ref "IC6") (pin "1") (pinfunction "OC_1") (pintype "input"))
    )
    (net (code "78") (name "Net-(IC4F-O)") (class "Default")
      (node (ref "IC4") (pin "12") (pinfunction "O_12") (pintype "output"))
      (node (ref "R24") (pin "2") (pinfunction "2_2") (pintype "passive"))
    )
    (net (code "79") (name "Net-(IC12-VI)") (class "Default")
      (node (ref "C1") (pin "+") (pinfunction "+_+") (pintype "passive"))
      (node (ref "C2") (pin "1") (pinfunction "1_1") (pintype "passive"))
      (node (ref "D1") (pin "C") (pinfunction "C_C") (pintype "passive"))
      (node (ref "IC12") (pin "1") (pinfunction "VI_1") (pintype "input"))
    )
    (net (code "80") (name "Net-(IC13-~{CEO})") (class "Default")
      (node (ref "IC13") (pin "6") (pinfunction "~{CEO}_6") (pintype "bidirectional"))
      (node (ref "R19") (pin "2") (pinfunction "2_2") (pintype "passive"))
      (node (ref "R20") (pin "2") (pinfunction "2_2") (pintype "passive"))
    )
    (net (code "81") (name "Net-(IC14-A)") (class "Default")
      (node (ref "D2") (pin "C") (pinfunction "C_C") (pintype "passive"))
      (node (ref "IC14") (pin "2") (pinfunction "A_2") (pintype "passive"))
      (node (ref "R16") (pin "2") (pinfunction "2_2") (pintype "passive"))
    )
    (net (code "82") (name "Net-(IC14-C)") (class "Default")
      (node (ref "D2") (pin "A") (pinfunction "A_A") (pintype "passive"))
      (node (ref "IC14") (pin "3") (pinfunction "C_3") (pintype "passive"))
      (node (ref "X2") (pin "5") (pinfunction "5_5") (pintype "passive"))
    )
    (net (code "83") (name "Net-(IC14-VB)") (class "Default")
      (node (ref "IC14") (pin "7") (pinfunction "VB_7") (pintype "passive"))
      (node (ref "R17") (pin "2") (pinfunction "2_2") (pintype "passive"))
    )
    (net (code "84") (name "Net-(J1-PadPWR)") (class "Default")
      (node (ref "J1") (pin "PWR") (pinfunction "PWR_PWR") (pintype "bidirectional"))
      (node (ref "S1") (pin "2") (pinfunction "2_2") (pintype "passive"))
    )
    (net (code "85") (name "Net-(Q1-B)") (class "Default")
      (node (ref "Q1") (pin "2") (pinfunction "B_2") (pintype "passive"))
      (node (ref "R19") (pin "1") (pinfunction "1_1") (pintype "passive"))
    )
    (net (code "86") (name "Net-(Q2-B)") (class "Default")
      (node (ref "Q2") (pin "2") (pinfunction "B_2") (pintype "passive"))
      (node (ref "R20") (pin "1") (pinfunction "1_1") (pintype "passive"))
    )
    (net (code "87") (name "Net-(R16-Pad1)") (class "Default")
      (node (ref "R16") (pin "1") (pinfunction "1_1") (pintype "passive"))
      (node (ref "X2") (pin "4") (pinfunction "4_4") (pintype "passive"))
    )
    (net (code "88") (name "Net-(R24-Pad1)") (class "Default")
      (node (ref "R24") (pin "1") (pinfunction "1_1") (pintype "passive"))
      (node (ref "X3") (pin "4") (pinfunction "4_4") (pintype "passive"))
    )
    (net (code "89") (name "Net-(R25-Pad1)") (class "Default")
      (node (ref "R25") (pin "1") (pinfunction "1_1") (pintype "passive"))
      (node (ref "X3") (pin "5") (pinfunction "5_5") (pintype "passive"))
    )
    (net (code "90") (name "Net-(VR1B-2)") (class "Default")
      (node (ref "C9") (pin "-") (pinfunction "-_-") (pintype "passive"))
      (node (ref "VR1") (pin "O1") (pinfunction "2_O1") (pintype "passive"))
    )
    (net (code "91") (name "Net-(VR1B-3)") (class "Default")
      (node (ref "C8") (pin "-") (pinfunction "-_-") (pintype "passive"))
      (node (ref "VR1") (pin "I1") (pinfunction "3_I1") (pintype "passive"))
    )
    (net (code "92") (name "Net-(VR1C-2)") (class "Default")
      (node (ref "C12") (pin "-") (pinfunction "-_-") (pintype "passive"))
      (node (ref "VR1") (pin "O2") (pinfunction "2_O2") (pintype "passive"))
    )
    (net (code "93") (name "Net-(VR1C-3)") (class "Default")
      (node (ref "C11") (pin "-") (pinfunction "-_-") (pintype "passive"))
      (node (ref "VR1") (pin "I2") (pinfunction "3_I2") (pintype "passive"))
    )
    (net (code "94") (name "RAW1") (class "Default")
      (node (ref "C8") (pin "+") (pinfunction "+_+") (pintype "passive"))
      (node (ref "IC2") (pin "1") (pinfunction "SND1_1") (pintype "output"))
      (node (ref "R3") (pin "2") (pinfunction "2_2") (pintype "passive"))
    )
    (net (code "95") (name "RAW2") (class "Default")
      (node (ref "C11") (pin "+") (pinfunction "+_+") (pintype "passive"))
      (node (ref "IC2") (pin "2") (pinfunction "SND2_2") (pintype "output"))
      (node (ref "R4") (pin "2") (pinfunction "2_2") (pintype "passive"))
    )
    (net (code "96") (name "RESET") (class "Default")
      (node (ref "C7") (pin "2") (pinfunction "2_2") (pintype "passive"))
      (node (ref "IC1") (pin "1") (pinfunction "PC6(/RESET)_1") (pintype "bidirectional"))
      (node (ref "R1") (pin "1") (pinfunction "1_1") (pintype "passive"))
      (node (ref "SV1") (pin "5") (pinfunction "5_5") (pintype "passive"))
    )
    (net (code "97") (name "ROW_EN") (class "Default")
      (node (ref "IC5") (pin "13") (pinfunction "Y2_13") (pintype "output"))
      (node (ref "SV2") (pin "8") (pinfunction "8_8") (pintype "passive"))
    )
    (net (code "98") (name "R{slash}W") (class "Default")
      (node (ref "IC1") (pin "26") (pinfunction "PC3(ADC3)_26") (pintype "bidirectional"))
      (node (ref "IC2") (pin "34") (pinfunction "R/W_34") (pintype "input"))
      (node (ref "IC4") (pin "11") (pinfunction "I_11") (pintype "input"))
    )
    (net (code "99") (name "SCK") (class "Default")
      (node (ref "IC1") (pin "19") (pinfunction "PB5(SCK)_19") (pintype "bidirectional"))
      (node (ref "SV1") (pin "3") (pinfunction "3_3") (pintype "passive"))
    )
    (net (code "100") (name "SWITCHCOL_EN") (class "Default")
      (node (ref "IC4") (pin "8") (pinfunction "O_8") (pintype "output"))
      (node (ref "SV2") (pin "10") (pinfunction "10_10") (pintype "passive"))
    )
    (net (code "101") (name "VBAT") (class "Default")
      (node (ref "IC1") (pin "28") (pinfunction "PC5(ADC5/SCL)_28") (pintype "bidirectional"))
      (node (ref "IC3") (pin "13") (pinfunction "-IN_13") (pintype "input"))
      (node (ref "IC3") (pin "14") (pinfunction "OUT_14") (pintype "output"))
    )
    (net (code "102") (name "VCC") (class "Default")
      (node (ref "C15") (pin "1") (pinfunction "1_1") (pintype "passive"))
      (node (ref "C16") (pin "1") (pinfunction "1_1") (pintype "passive"))
      (node (ref "C17") (pin "1") (pinfunction "1_1") (pintype "passive"))
      (node (ref "C18") (pin "1") (pinfunction "1_1") (pintype "passive"))
      (node (ref "C19") (pin "1") (pinfunction "1_1") (pintype "passive"))
      (node (ref "C20") (pin "1") (pinfunction "1_1") (pintype "passive"))
      (node (ref "C21") (pin "1") (pinfunction "1_1") (pintype "passive"))
      (node (ref "C22") (pin "1") (pinfunction "1_1") (pintype "passive"))
      (node (ref "C23") (pin "1") (pinfunction "1_1") (pintype "passive"))
      (node (ref "C24") (pin "1") (pinfunction "1_1") (pintype "passive"))
      (node (ref "C25") (pin "1") (pinfunction "1_1") (pintype "passive"))
      (node (ref "C3") (pin "1") (pinfunction "1_1") (pintype "passive"))
      (node (ref "C4") (pin "+") (pinfunction "+_+") (pintype "passive"))
      (node (ref "IC1") (pin "20") (pinfunction "AVCC_20") (pintype "power_in"))
      (node (ref "IC1") (pin "7") (pinfunction "VCC_7") (pintype "power_in"))
      (node (ref "IC12") (pin "3") (pinfunction "VO_3") (pintype "passive"))
      (node (ref "IC13") (pin "8") (pinfunction "VCCI_8") (pintype "bidirectional"))
      (node (ref "IC14") (pin "8") (pinfunction "VCC_8") (pintype "passive"))
      (node (ref "IC2") (pin "40") (pinfunction "VDD_40") (pintype "power_in"))
      (node (ref "IC3") (pin "4") (pinfunction "V+_4") (pintype "power_in"))
      (node (ref "R1") (pin "2") (pinfunction "2_2") (pintype "passive"))
      (node (ref "R13") (pin "1") (pinfunction "1_1") (pintype "passive"))
      (node (ref "R18") (pin "2") (pinfunction "2_2") (pintype "passive"))
      (node (ref "R2") (pin "1") (pinfunction "1_1") (pintype "passive"))
      (node (ref "R5") (pin "2") (pinfunction "2_2") (pintype "passive"))
      (node (ref "SV1") (pin "2") (pinfunction "2_2") (pintype "passive"))
      (node (ref "SV2") (pin "14") (pinfunction "14_14") (pintype "passive"))
      (node (ref "SV2") (pin "16") (pinfunction "16_16") (pintype "passive"))
    )
    (net (code "103") (name "WE") (class "Default")
      (node (ref "IC1") (pin "27") (pinfunction "PC4(ADC4/SDA)_27") (pintype "bidirectional"))
      (node (ref "IC10") (pin "29") (pinfunction "WE_29") (pintype "input"))
      (node (ref "IC11") (pin "29") (pinfunction "WE_29") (pintype "input"))
      (node (ref "R5") (pin "1") (pinfunction "1_1") (pintype "passive"))
    )
    (net (code "104") (name "unconnected-(IC1-AREF-Pad21)") (class "Default")
      (node (ref "IC1") (pin "21") (pinfunction "AREF_21") (pintype "passive"))
    )
    (net (code "105") (name "unconnected-(IC2-A0-Pad4)") (class "Default")
      (node (ref "IC2") (pin "4") (pinfunction "A0_4") (pintype "output"))
    )
    (net (code "106") (name "unconnected-(IC2-A1-Pad5)") (class "Default")
      (node (ref "IC2") (pin "5") (pinfunction "A1_5") (pintype "output"))
    )
    (net (code "107") (name "unconnected-(IC2-A2-Pad6)") (class "Default")
      (node (ref "IC2") (pin "6") (pinfunction "A2_6") (pintype "output"))
    )
    (net (code "108") (name "unconnected-(IC2-A3-Pad7)") (class "Default")
      (node (ref "IC2") (pin "7") (pinfunction "A3_7") (pintype "output"))
    )
    (net (code "109") (name "unconnected-(IC2-A4-Pad8)") (class "Default")
      (node (ref "IC2") (pin "8") (pinfunction "A4_8") (pintype "output"))
    )
    (net (code "110") (name "unconnected-(IC2-A5-Pad9)") (class "Default")
      (node (ref "IC2") (pin "9") (pinfunction "A5_9") (pintype "output"))
    )
    (net (code "111") (name "unconnected-(IC2-A6-Pad10)") (class "Default")
      (node (ref "IC2") (pin "10") (pinfunction "A6_10") (pintype "output"))
    )
    (net (code "112") (name "unconnected-(IC2-A7-Pad11)") (class "Default")
      (node (ref "IC2") (pin "11") (pinfunction "A7_11") (pintype "output"))
    )
    (net (code "113") (name "unconnected-(IC2-A8-Pad12)") (class "Default")
      (node (ref "IC2") (pin "12") (pinfunction "A8_12") (pintype "output"))
    )
    (net (code "114") (name "unconnected-(IC2-A9-Pad13)") (class "Default")
      (node (ref "IC2") (pin "13") (pinfunction "A9_13") (pintype "output"))
    )
    (net (code "115") (name "unconnected-(IC2-A10-Pad14)") (class "Default")
      (node (ref "IC2") (pin "14") (pinfunction "A10_14") (pintype "output"))
    )
    (net (code "116") (name "unconnected-(IC2-A11-Pad15)") (class "Default")
      (node (ref "IC2") (pin "15") (pinfunction "A11_15") (pintype "output"))
    )
    (net (code "117") (name "unconnected-(IC2-A12-Pad16)") (class "Default")
      (node (ref "IC2") (pin "16") (pinfunction "A12_16") (pintype "bidirectional"))
    )
    (net (code "118") (name "unconnected-(IC2-A13-Pad17)") (class "Default")
      (node (ref "IC2") (pin "17") (pinfunction "A13_17") (pintype "bidirectional"))
    )
    (net (code "119") (name "unconnected-(IC2-A14-Pad18)") (class "Default")
      (node (ref "IC2") (pin "18") (pinfunction "A14_18") (pintype "bidirectional"))
    )
    (net (code "120") (name "unconnected-(IC2-A15-Pad19)") (class "Default")
      (node (ref "IC2") (pin "19") (pinfunction "A15_19") (pintype "bidirectional"))
    )
    (net (code "121") (name "unconnected-(IC2-EXT44-Pad38)") (class "Default")
      (node (ref "IC2") (pin "38") (pinfunction "EXT44_38") (pintype "bidirectional"))
    )
    (net (code "122") (name "unconnected-(IC2-EXT55-Pad37)") (class "Default")
      (node (ref "IC2") (pin "37") (pinfunction "EXT55_37") (pintype "bidirectional"))
    )
    (net (code "123") (name "unconnected-(IC2-M2-Pad31)") (class "Default")
      (node (ref "IC2") (pin "31") (pinfunction "M2_31") (pintype "input"))
    )
    (net (code "124") (name "unconnected-(IC2-STROBE-Pad39)") (class "Default")
      (node (ref "IC2") (pin "39") (pinfunction "STROBE_39") (pintype "bidirectional"))
    )
    (net (code "125") (name "unconnected-(IC2-{slash}OE1-Pad36)") (class "Default")
      (node (ref "IC2") (pin "36") (pinfunction "/OE1_36") (pintype "bidirectional"))
    )
    (net (code "126") (name "unconnected-(IC2-{slash}OE2-Pad35)") (class "Default")
      (node (ref "IC2") (pin "35") (pinfunction "/OE2_35") (pintype "input"))
    )
    (net (code "127") (name "unconnected-(IC5A-Y7-Pad7)") (class "Default")
      (node (ref "IC5") (pin "7") (pinfunction "Y7_7") (pintype "output"))
    )
    (net (code "128") (name "unconnected-(IC9A-6Q-Pad14)") (class "Default")
      (node (ref "IC9") (pin "14") (pinfunction "6Q_14") (pintype "tri_state"))
    )
    (net (code "129") (name "unconnected-(IC9A-7Q-Pad13)") (class "Default")
      (node (ref "IC9") (pin "13") (pinfunction "7Q_13") (pintype "tri_state"))
    )
    (net (code "130") (name "unconnected-(IC9A-8Q-Pad12)") (class "Default")
      (node (ref "IC9") (pin "12") (pinfunction "8Q_12") (pintype "tri_state"))
    )
    (net (code "131") (name "unconnected-(J2-PadSN)") (class "Default")
      (node (ref "J2") (pin "SN") (pinfunction "SN_SN") (pintype "passive"))
    )
    (net (code "132") (name "unconnected-(J2-PadTN)") (class "Default")
      (node (ref "J2") (pin "TN") (pinfunction "TN_TN") (pintype "passive"))
    )
    (net (code "133") (name "unconnected-(J3-PadSN)") (class "Default")
      (node (ref "J3") (pin "SN") (pinfunction "SN_SN") (pintype "passive"))
    )
    (net (code "134") (name "unconnected-(J3-PadTN)") (class "Default")
      (node (ref "J3") (pin "TN") (pinfunction "TN_TN") (pintype "passive"))
    )
    (net (code "135") (name "unconnected-(S1-Pad1)") (class "Default")
      (node (ref "S1") (pin "1") (pinfunction "1_1") (pintype "passive"))
    )
    (net (code "136") (name "unconnected-(X2-Pad1)") (class "Default")
      (node (ref "X2") (pin "1") (pinfunction "1_1") (pintype "passive"))
    )
    (net (code "137") (name "unconnected-(X2-Pad2)") (class "Default")
      (node (ref "X2") (pin "2") (pinfunction "2_2") (pintype "passive"))
    )
    (net (code "138") (name "unconnected-(X2-Pad3)") (class "Default")
      (node (ref "X2") (pin "3") (pinfunction "3_3") (pintype "passive"))
    )
    (net (code "139") (name "unconnected-(X3-Pad1)") (class "Default")
      (node (ref "X3") (pin "1") (pinfunction "1_1") (pintype "passive"))
    )
    (net (code "140") (name "unconnected-(X3-Pad3)") (class "Default")
      (node (ref "X3") (pin "3") (pinfunction "3_3") (pintype "passive"))
    )
    (net (code "141") (name "{slash}RES") (class "Default")
      (node (ref "IC1") (pin "25") (pinfunction "PC2(ADC2)_25") (pintype "bidirectional"))
      (node (ref "IC2") (pin "3") (pinfunction "/RST_3") (pintype "output"))
    )
  )
)
